# ab-berry.net
KiCad netlist of a schematic drawn in EAGLE
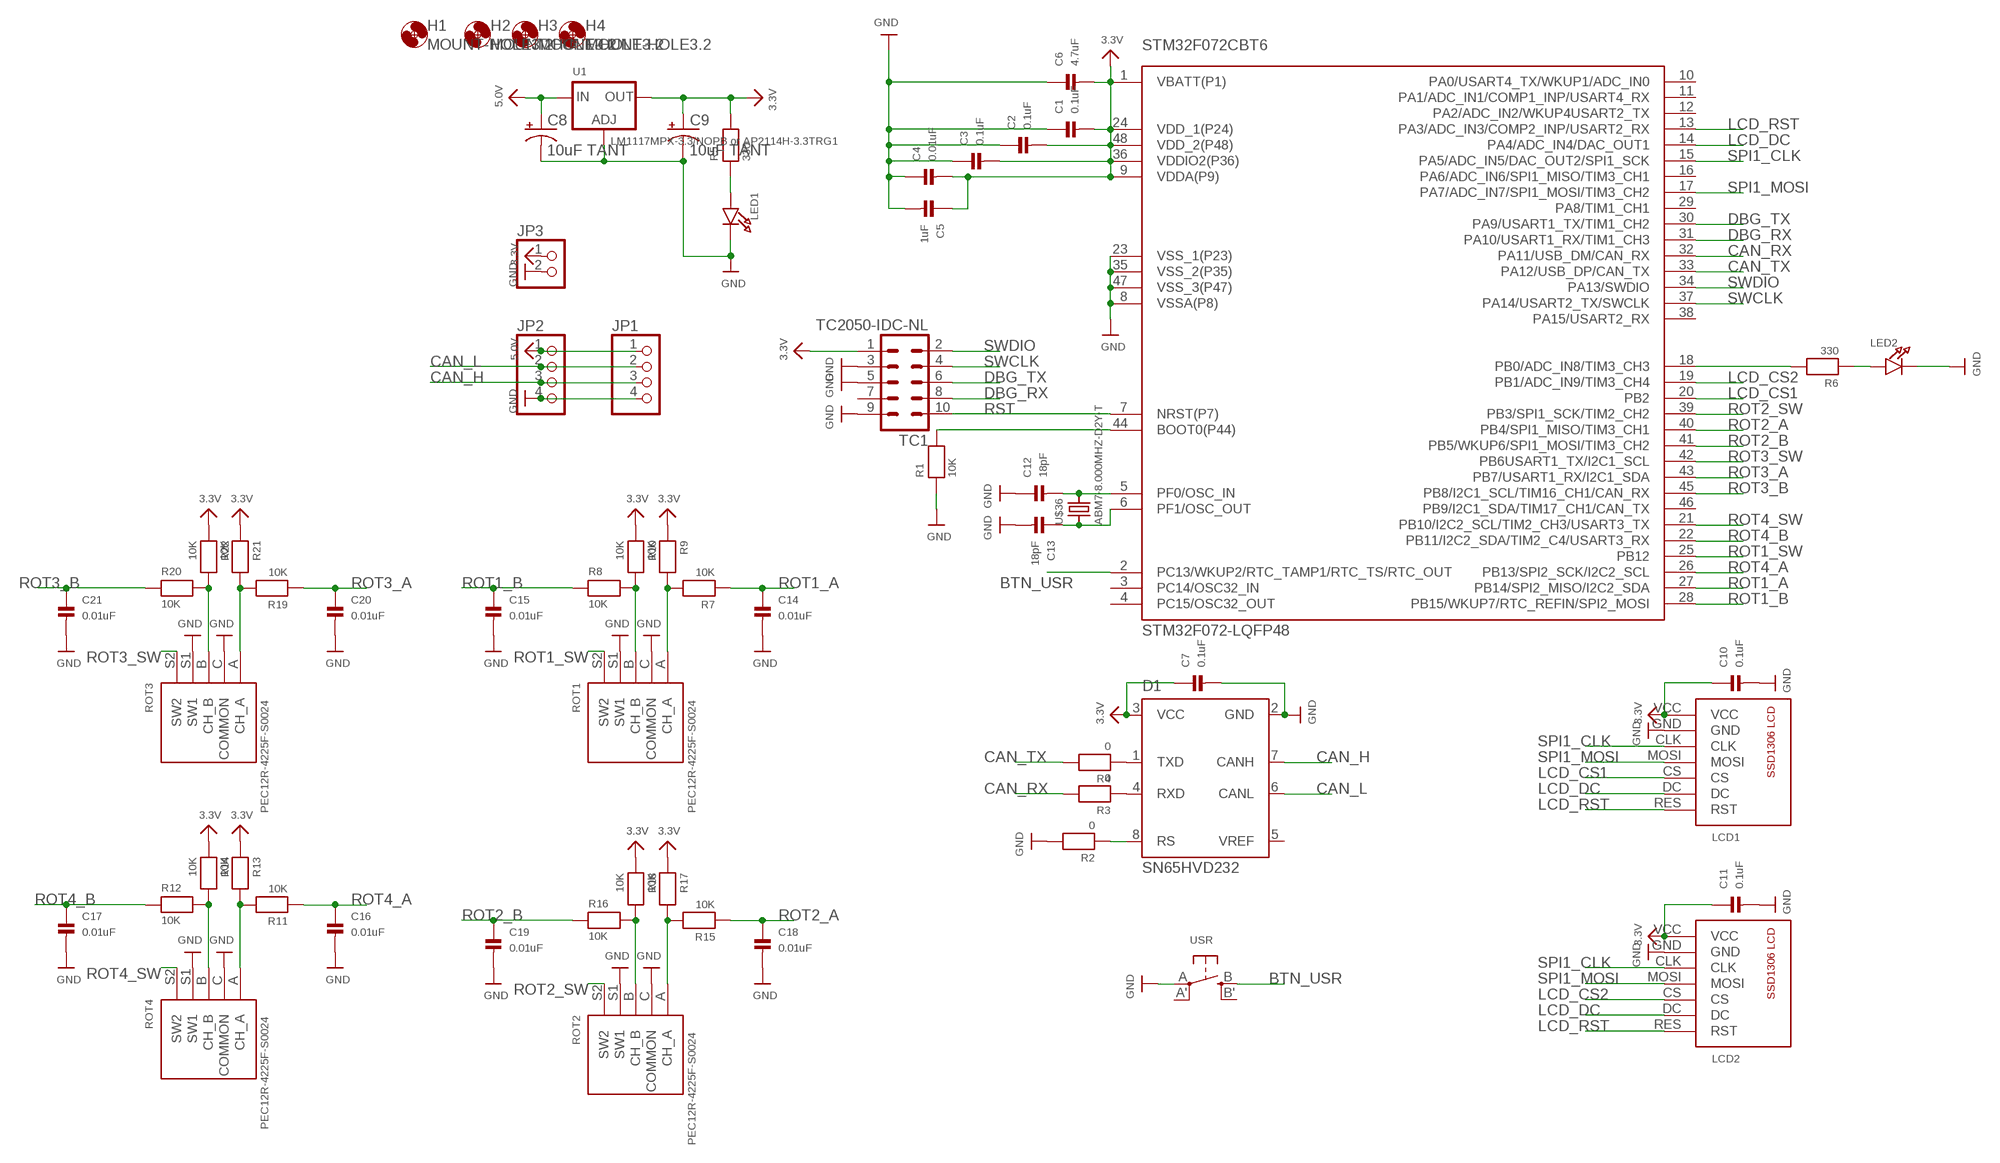
[diagram p0: schematic, sheet 1]

(export (version "E")
  (design (tool "Eeschema 10.0.6"))
  (components
    (comp (ref "C1")
      (value "0.1uF")
      (footprint "eagle-import:0603")
      (libsource (lib "eagle-import") (part "CAP_CERAMIC0603"))
    )
    (comp (ref "C2")
      (value "0.1uF")
      (footprint "eagle-import:0603")
      (libsource (lib "eagle-import") (part "CAP_CERAMIC0603"))
    )
    (comp (ref "C3")
      (value "0.1uF")
      (footprint "eagle-import:0603")
      (libsource (lib "eagle-import") (part "CAP_CERAMIC0603"))
    )
    (comp (ref "C4")
      (value "0.01uF")
      (footprint "eagle-import:0603")
      (libsource (lib "eagle-import") (part "CAP_CERAMIC0603"))
    )
    (comp (ref "C5")
      (value "1uF")
      (footprint "eagle-import:0603")
      (libsource (lib "eagle-import") (part "CAP_CERAMIC0603"))
    )
    (comp (ref "C6")
      (value "4.7uF")
      (footprint "eagle-import:0603")
      (libsource (lib "eagle-import") (part "CAP_CERAMIC0603"))
    )
    (comp (ref "C7")
      (value "0.1uF")
      (footprint "eagle-import:0603")
      (libsource (lib "eagle-import") (part "CAP_CERAMIC0603"))
    )
    (comp (ref "C8")
      (value "10uF TANT")
      (footprint "eagle-import:0603-POL")
      (libsource (lib "eagle-import") (part "10UF-6.3V-20%(0603)(TANT){dblquote}"))
    )
    (comp (ref "C9")
      (value "10uF TANT")
      (footprint "eagle-import:0603-POL")
      (libsource (lib "eagle-import") (part "10UF-6.3V-20%(0603)(TANT){dblquote}"))
    )
    (comp (ref "C10")
      (value "0.1uF")
      (footprint "eagle-import:0603")
      (libsource (lib "eagle-import") (part "CAP_CERAMIC0603"))
    )
    (comp (ref "C11")
      (value "0.1uF")
      (footprint "eagle-import:0603")
      (libsource (lib "eagle-import") (part "CAP_CERAMIC0603"))
    )
    (comp (ref "C12")
      (value "18pF")
      (footprint "eagle-import:0603")
      (libsource (lib "eagle-import") (part "CAP_CERAMIC0603"))
    )
    (comp (ref "C13")
      (value "18pF")
      (footprint "eagle-import:0603")
      (libsource (lib "eagle-import") (part "CAP_CERAMIC0603"))
    )
    (comp (ref "C14")
      (value "0.01uF")
      (footprint "eagle-import:0603")
      (libsource (lib "eagle-import") (part "CAP_CERAMIC0603"))
    )
    (comp (ref "C15")
      (value "0.01uF")
      (footprint "eagle-import:0603")
      (libsource (lib "eagle-import") (part "CAP_CERAMIC0603"))
    )
    (comp (ref "C16")
      (value "0.01uF")
      (footprint "eagle-import:0603")
      (libsource (lib "eagle-import") (part "CAP_CERAMIC0603"))
    )
    (comp (ref "C17")
      (value "0.01uF")
      (footprint "eagle-import:0603")
      (libsource (lib "eagle-import") (part "CAP_CERAMIC0603"))
    )
    (comp (ref "C18")
      (value "0.01uF")
      (footprint "eagle-import:0603")
      (libsource (lib "eagle-import") (part "CAP_CERAMIC0603"))
    )
    (comp (ref "C19")
      (value "0.01uF")
      (footprint "eagle-import:0603")
      (libsource (lib "eagle-import") (part "CAP_CERAMIC0603"))
    )
    (comp (ref "C20")
      (value "0.01uF")
      (footprint "eagle-import:0603")
      (libsource (lib "eagle-import") (part "CAP_CERAMIC0603"))
    )
    (comp (ref "C21")
      (value "0.01uF")
      (footprint "eagle-import:0603")
      (libsource (lib "eagle-import") (part "CAP_CERAMIC0603"))
    )
    (comp (ref "D1")
      (value "SN65HVD232")
      (footprint "eagle-import:SO8")
      (libsource (lib "eagle-import") (part "SN65HVD230"))
    )
    (comp (ref "H1")
      (value "MOUNT-HOLE3.2")
      (footprint "eagle-import:3,2")
      (libsource (lib "eagle-import") (part "MOUNT-HOLE3.2"))
    )
    (comp (ref "H2")
      (value "MOUNT-HOLE3.2")
      (footprint "eagle-import:3,2")
      (libsource (lib "eagle-import") (part "MOUNT-HOLE3.2"))
    )
    (comp (ref "H3")
      (value "MOUNT-HOLE3.2")
      (footprint "eagle-import:3,2")
      (libsource (lib "eagle-import") (part "MOUNT-HOLE3.2"))
    )
    (comp (ref "H4")
      (value "MOUNT-HOLE3.2")
      (footprint "eagle-import:3,2")
      (libsource (lib "eagle-import") (part "MOUNT-HOLE3.2"))
    )
    (comp (ref "JP1")
      (value "PINHD-1X4")
      (footprint "eagle-import:1X04")
      (libsource (lib "eagle-import") (part "PINHD-1X4"))
    )
    (comp (ref "JP2")
      (value "PINHD-1X4")
      (footprint "eagle-import:1X04")
      (libsource (lib "eagle-import") (part "PINHD-1X4"))
    )
    (comp (ref "JP3")
      (value "PINHD-1X2")
      (footprint "eagle-import:1X02")
      (libsource (lib "eagle-import") (part "PINHD-1X2"))
    )
    (comp (ref "LCD1")
      (value "SSD1306-7PIN")
      (footprint "eagle-import:SSD1306-7PIN")
      (libsource (lib "eagle-import") (part "SSD1306-7PIN"))
    )
    (comp (ref "LCD2")
      (value "SSD1306-7PIN")
      (footprint "eagle-import:SSD1306-7PIN")
      (libsource (lib "eagle-import") (part "SSD1306-7PIN"))
    )
    (comp (ref "LED1")
      (value "LED0603")
      (footprint "eagle-import:CHIPLED_0603")
      (libsource (lib "eagle-import") (part "LED0603"))
    )
    (comp (ref "LED2")
      (value "LED0603")
      (footprint "eagle-import:CHIPLED_0603")
      (libsource (lib "eagle-import") (part "LED0603"))
    )
    (comp (ref "R1")
      (value "10K")
      (footprint "eagle-import:0603")
      (libsource (lib "eagle-import") (part "RESISTOR0603"))
    )
    (comp (ref "R2")
      (value "0")
      (footprint "eagle-import:0603")
      (libsource (lib "eagle-import") (part "RESISTOR0603"))
    )
    (comp (ref "R3")
      (value "0")
      (footprint "eagle-import:0603")
      (libsource (lib "eagle-import") (part "RESISTOR0603"))
    )
    (comp (ref "R4")
      (value "0")
      (footprint "eagle-import:0603")
      (libsource (lib "eagle-import") (part "RESISTOR0603"))
    )
    (comp (ref "R5")
      (value "330")
      (footprint "eagle-import:0603")
      (libsource (lib "eagle-import") (part "RESISTOR0603"))
    )
    (comp (ref "R6")
      (value "330")
      (footprint "eagle-import:0603")
      (libsource (lib "eagle-import") (part "RESISTOR0603"))
    )
    (comp (ref "R7")
      (value "10K")
      (footprint "eagle-import:0603")
      (libsource (lib "eagle-import") (part "RESISTOR0603"))
    )
    (comp (ref "R8")
      (value "10K")
      (footprint "eagle-import:0603")
      (libsource (lib "eagle-import") (part "RESISTOR0603"))
    )
    (comp (ref "R9")
      (value "10K")
      (footprint "eagle-import:0603")
      (libsource (lib "eagle-import") (part "RESISTOR0603"))
    )
    (comp (ref "R10")
      (value "10K")
      (footprint "eagle-import:0603")
      (libsource (lib "eagle-import") (part "RESISTOR0603"))
    )
    (comp (ref "R11")
      (value "10K")
      (footprint "eagle-import:0603")
      (libsource (lib "eagle-import") (part "RESISTOR0603"))
    )
    (comp (ref "R12")
      (value "10K")
      (footprint "eagle-import:0603")
      (libsource (lib "eagle-import") (part "RESISTOR0603"))
    )
    (comp (ref "R13")
      (value "10K")
      (footprint "eagle-import:0603")
      (libsource (lib "eagle-import") (part "RESISTOR0603"))
    )
    (comp (ref "R14")
      (value "10K")
      (footprint "eagle-import:0603")
      (libsource (lib "eagle-import") (part "RESISTOR0603"))
    )
    (comp (ref "R15")
      (value "10K")
      (footprint "eagle-import:0603")
      (libsource (lib "eagle-import") (part "RESISTOR0603"))
    )
    (comp (ref "R16")
      (value "10K")
      (footprint "eagle-import:0603")
      (libsource (lib "eagle-import") (part "RESISTOR0603"))
    )
    (comp (ref "R17")
      (value "10K")
      (footprint "eagle-import:0603")
      (libsource (lib "eagle-import") (part "RESISTOR0603"))
    )
    (comp (ref "R18")
      (value "10K")
      (footprint "eagle-import:0603")
      (libsource (lib "eagle-import") (part "RESISTOR0603"))
    )
    (comp (ref "R19")
      (value "10K")
      (footprint "eagle-import:0603")
      (libsource (lib "eagle-import") (part "RESISTOR0603"))
    )
    (comp (ref "R20")
      (value "10K")
      (footprint "eagle-import:0603")
      (libsource (lib "eagle-import") (part "RESISTOR0603"))
    )
    (comp (ref "R21")
      (value "10K")
      (footprint "eagle-import:0603")
      (libsource (lib "eagle-import") (part "RESISTOR0603"))
    )
    (comp (ref "R22")
      (value "10K")
      (footprint "eagle-import:0603")
      (libsource (lib "eagle-import") (part "RESISTOR0603"))
    )
    (comp (ref "ROT1")
      (value "PEC12R-4225F-S0024")
      (footprint "eagle-import:PEC111-4XXXK-SXXXX")
      (libsource (lib "eagle-import") (part "PEC11-4215K-S0024"))
    )
    (comp (ref "ROT2")
      (value "PEC12R-4225F-S0024")
      (footprint "eagle-import:PEC111-4XXXK-SXXXX")
      (libsource (lib "eagle-import") (part "PEC11-4215K-S0024"))
    )
    (comp (ref "ROT3")
      (value "PEC12R-4225F-S0024")
      (footprint "eagle-import:PEC111-4XXXK-SXXXX")
      (libsource (lib "eagle-import") (part "PEC11-4215K-S0024"))
    )
    (comp (ref "ROT4")
      (value "PEC12R-4225F-S0024")
      (footprint "eagle-import:PEC111-4XXXK-SXXXX")
      (libsource (lib "eagle-import") (part "PEC11-4215K-S0024"))
    )
    (comp (ref "STM32F072CBT6")
      (value "STM32F072-LQFP48")
      (footprint "eagle-import:LQFP48")
      (libsource (lib "eagle-import") (part "STM32F072-LQFP48"))
    )
    (comp (ref "TC1")
      (value "TC2050-IDC-NL")
      (footprint "eagle-import:TC2050-IDC-NL")
      (libsource (lib "eagle-import") (part "TC2050-IDC-NL"))
    )
    (comp (ref "U$36")
      (value "ABM7-8.000MHZ-D2Y-T")
      (footprint "eagle-import:ABM7-8.000MHZ-D2Y-T")
      (libsource (lib "eagle-import") (part "ABM7-8.000MHZ-D2Y-T"))
    )
    (comp (ref "U1")
      (value "LM1117MPX-3.3/NOPB or AP2114H-3.3TRG1")
      (footprint "eagle-import:SOT223-R")
      (libsource (lib "eagle-import") (part "LM1117SOT223-REFLOW"))
    )
    (comp (ref "USR")
      (value "SWITCH_TACT_SMT")
      (footprint "eagle-import:EVQ-Q2")
      (libsource (lib "eagle-import") (part "SWITCH_TACT_SMT"))
    )
  )
  (nets
    (net (code "1") (name "/BTN_USR") (class "Default")
      (node (ref "STM32F072CBT6") (pin "2") (pinfunction "PC13/WKUP2/RTC_TAMP1/RTC_TS/RTC_OUT_2") (pintype "bidirectional"))
      (node (ref "USR") (pin "B") (pinfunction "S_B") (pintype "passive"))
    )
    (net (code "2") (name "/CAN_H") (class "Default")
      (node (ref "D1") (pin "7") (pinfunction "CANH_7") (pintype "bidirectional"))
      (node (ref "JP1") (pin "3") (pinfunction "3_3") (pintype "passive"))
      (node (ref "JP2") (pin "3") (pinfunction "3_3") (pintype "passive"))
    )
    (net (code "3") (name "/CAN_L") (class "Default")
      (node (ref "D1") (pin "6") (pinfunction "CANL_6") (pintype "bidirectional"))
      (node (ref "JP1") (pin "2") (pinfunction "2_2") (pintype "passive"))
      (node (ref "JP2") (pin "2") (pinfunction "2_2") (pintype "passive"))
    )
    (net (code "4") (name "/CAN_RX") (class "Default")
      (node (ref "R3") (pin "2") (pinfunction "2_2") (pintype "passive"))
      (node (ref "STM32F072CBT6") (pin "32") (pinfunction "PA11/USB_DM/CAN_RX_32") (pintype "bidirectional"))
    )
    (net (code "5") (name "/CAN_TX") (class "Default")
      (node (ref "R4") (pin "2") (pinfunction "2_2") (pintype "passive"))
      (node (ref "STM32F072CBT6") (pin "33") (pinfunction "PA12/USB_DP/CAN_TX_33") (pintype "bidirectional"))
    )
    (net (code "6") (name "/DBG_RX") (class "Default")
      (node (ref "STM32F072CBT6") (pin "31") (pinfunction "PA10/USART1_RX/TIM1_CH3_31") (pintype "bidirectional"))
      (node (ref "TC1") (pin "8") (pinfunction "8_8") (pintype "passive"))
    )
    (net (code "7") (name "/DBG_TX") (class "Default")
      (node (ref "STM32F072CBT6") (pin "30") (pinfunction "PA9/USART1_TX/TIM1_CH2_30") (pintype "bidirectional"))
      (node (ref "TC1") (pin "6") (pinfunction "6_6") (pintype "passive"))
    )
    (net (code "8") (name "/LCD_CS1") (class "Default")
      (node (ref "LCD1") (pin "CS") (pinfunction "CS_CS") (pintype "bidirectional"))
      (node (ref "STM32F072CBT6") (pin "20") (pinfunction "PB2_20") (pintype "bidirectional"))
    )
    (net (code "9") (name "/LCD_CS2") (class "Default")
      (node (ref "LCD2") (pin "CS") (pinfunction "CS_CS") (pintype "bidirectional"))
      (node (ref "STM32F072CBT6") (pin "19") (pinfunction "PB1/ADC_IN9/TIM3_CH4_19") (pintype "bidirectional"))
    )
    (net (code "10") (name "/LCD_DC") (class "Default")
      (node (ref "LCD1") (pin "DC") (pinfunction "DC_DC") (pintype "bidirectional"))
      (node (ref "LCD2") (pin "DC") (pinfunction "DC_DC") (pintype "bidirectional"))
      (node (ref "STM32F072CBT6") (pin "14") (pinfunction "PA4/ADC_IN4/DAC_OUT1_14") (pintype "bidirectional"))
    )
    (net (code "11") (name "/LCD_RST") (class "Default")
      (node (ref "LCD1") (pin "RES") (pinfunction "RST_RES") (pintype "bidirectional"))
      (node (ref "LCD2") (pin "RES") (pinfunction "RST_RES") (pintype "bidirectional"))
      (node (ref "STM32F072CBT6") (pin "13") (pinfunction "PA3/ADC_IN3/COMP2_INP/USART2_RX_13") (pintype "bidirectional"))
    )
    (net (code "12") (name "/ROT1_A") (class "Default")
      (node (ref "C14") (pin "1") (pinfunction "P$1_1") (pintype "passive"))
      (node (ref "R7") (pin "1") (pinfunction "1_1") (pintype "passive"))
      (node (ref "STM32F072CBT6") (pin "27") (pinfunction "PB14/SPI2_MISO/I2C2_SDA_27") (pintype "bidirectional"))
    )
    (net (code "13") (name "/ROT1_B") (class "Default")
      (node (ref "C15") (pin "1") (pinfunction "P$1_1") (pintype "passive"))
      (node (ref "R8") (pin "1") (pinfunction "1_1") (pintype "passive"))
      (node (ref "STM32F072CBT6") (pin "28") (pinfunction "PB15/WKUP7/RTC_REFIN/SPI2_MOSI_28") (pintype "bidirectional"))
    )
    (net (code "14") (name "/ROT1_SW") (class "Default")
      (node (ref "ROT1") (pin "S2") (pinfunction "SW2_S2") (pintype "bidirectional"))
      (node (ref "STM32F072CBT6") (pin "25") (pinfunction "PB12_25") (pintype "bidirectional"))
    )
    (net (code "15") (name "/ROT2_A") (class "Default")
      (node (ref "C18") (pin "1") (pinfunction "P$1_1") (pintype "passive"))
      (node (ref "R15") (pin "1") (pinfunction "1_1") (pintype "passive"))
      (node (ref "STM32F072CBT6") (pin "40") (pinfunction "PB4/SPI1_MISO/TIM3_CH1_40") (pintype "bidirectional"))
    )
    (net (code "16") (name "/ROT2_B") (class "Default")
      (node (ref "C19") (pin "1") (pinfunction "P$1_1") (pintype "passive"))
      (node (ref "R16") (pin "1") (pinfunction "1_1") (pintype "passive"))
      (node (ref "STM32F072CBT6") (pin "41") (pinfunction "PB5/WKUP6/SPI1_MOSI/TIM3_CH2_41") (pintype "bidirectional"))
    )
    (net (code "17") (name "/ROT2_SW") (class "Default")
      (node (ref "ROT2") (pin "S2") (pinfunction "SW2_S2") (pintype "bidirectional"))
      (node (ref "STM32F072CBT6") (pin "39") (pinfunction "PB3/SPI1_SCK/TIM2_CH2_39") (pintype "bidirectional"))
    )
    (net (code "18") (name "/ROT3_A") (class "Default")
      (node (ref "C20") (pin "1") (pinfunction "P$1_1") (pintype "passive"))
      (node (ref "R19") (pin "1") (pinfunction "1_1") (pintype "passive"))
      (node (ref "STM32F072CBT6") (pin "43") (pinfunction "PB7/USART1_RX/I2C1_SDA_43") (pintype "bidirectional"))
    )
    (net (code "19") (name "/ROT3_B") (class "Default")
      (node (ref "C21") (pin "1") (pinfunction "P$1_1") (pintype "passive"))
      (node (ref "R20") (pin "1") (pinfunction "1_1") (pintype "passive"))
      (node (ref "STM32F072CBT6") (pin "45") (pinfunction "PB8/I2C1_SCL/TIM16_CH1/CAN_RX_45") (pintype "bidirectional"))
    )
    (net (code "20") (name "/ROT3_SW") (class "Default")
      (node (ref "ROT3") (pin "S2") (pinfunction "SW2_S2") (pintype "bidirectional"))
      (node (ref "STM32F072CBT6") (pin "42") (pinfunction "PB6USART1_TX/I2C1_SCL_42") (pintype "bidirectional"))
    )
    (net (code "21") (name "/ROT4_A") (class "Default")
      (node (ref "C16") (pin "1") (pinfunction "P$1_1") (pintype "passive"))
      (node (ref "R11") (pin "1") (pinfunction "1_1") (pintype "passive"))
      (node (ref "STM32F072CBT6") (pin "26") (pinfunction "PB13/SPI2_SCK/I2C2_SCL_26") (pintype "bidirectional"))
    )
    (net (code "22") (name "/ROT4_B") (class "Default")
      (node (ref "C17") (pin "1") (pinfunction "P$1_1") (pintype "passive"))
      (node (ref "R12") (pin "1") (pinfunction "1_1") (pintype "passive"))
      (node (ref "STM32F072CBT6") (pin "22") (pinfunction "PB11/I2C2_SDA/TIM2_C4/USART3_RX_22") (pintype "bidirectional"))
    )
    (net (code "23") (name "/ROT4_SW") (class "Default")
      (node (ref "ROT4") (pin "S2") (pinfunction "SW2_S2") (pintype "bidirectional"))
      (node (ref "STM32F072CBT6") (pin "21") (pinfunction "PB10/I2C2_SCL/TIM2_CH3/USART3_TX_21") (pintype "bidirectional"))
    )
    (net (code "24") (name "/RST") (class "Default")
      (node (ref "STM32F072CBT6") (pin "7") (pinfunction "NRST(P7)_7") (pintype "bidirectional"))
      (node (ref "TC1") (pin "10") (pinfunction "10_10") (pintype "passive"))
    )
    (net (code "25") (name "/SPI1_CLK") (class "Default")
      (node (ref "LCD1") (pin "CLK") (pinfunction "CLK_CLK") (pintype "bidirectional"))
      (node (ref "LCD2") (pin "CLK") (pinfunction "CLK_CLK") (pintype "bidirectional"))
      (node (ref "STM32F072CBT6") (pin "15") (pinfunction "PA5/ADC_IN5/DAC_OUT2/SPI1_SCK_15") (pintype "bidirectional"))
    )
    (net (code "26") (name "/SPI1_MOSI") (class "Default")
      (node (ref "LCD1") (pin "MOSI") (pinfunction "MOSI_MOSI") (pintype "bidirectional"))
      (node (ref "LCD2") (pin "MOSI") (pinfunction "MOSI_MOSI") (pintype "bidirectional"))
      (node (ref "STM32F072CBT6") (pin "17") (pinfunction "PA7/ADC_IN7/SPI1_MOSI/TIM3_CH2_17") (pintype "bidirectional"))
    )
    (net (code "27") (name "/SWCLK") (class "Default")
      (node (ref "STM32F072CBT6") (pin "37") (pinfunction "PA14/USART2_TX/SWCLK_37") (pintype "bidirectional"))
      (node (ref "TC1") (pin "4") (pinfunction "4_4") (pintype "passive"))
    )
    (net (code "28") (name "/SWDIO") (class "Default")
      (node (ref "STM32F072CBT6") (pin "34") (pinfunction "PA13/SWDIO_34") (pintype "bidirectional"))
      (node (ref "TC1") (pin "2") (pinfunction "2_2") (pintype "passive"))
    )
    (net (code "29") (name "3.3V") (class "Default")
      (node (ref "C1") (pin "2") (pinfunction "P$2_2") (pintype "passive"))
      (node (ref "C10") (pin "1") (pinfunction "P$1_1") (pintype "passive"))
      (node (ref "C11") (pin "1") (pinfunction "P$1_1") (pintype "passive"))
      (node (ref "C2") (pin "2") (pinfunction "P$2_2") (pintype "passive"))
      (node (ref "C3") (pin "2") (pinfunction "P$2_2") (pintype "passive"))
      (node (ref "C4") (pin "2") (pinfunction "P$2_2") (pintype "passive"))
      (node (ref "C5") (pin "1") (pinfunction "P$1_1") (pintype "passive"))
      (node (ref "C6") (pin "2") (pinfunction "P$2_2") (pintype "passive"))
      (node (ref "C7") (pin "1") (pinfunction "P$1_1") (pintype "passive"))
      (node (ref "C9") (pin "A") (pinfunction "+_A") (pintype "passive"))
      (node (ref "D1") (pin "3") (pinfunction "VCC_3") (pintype "power_in"))
      (node (ref "JP3") (pin "1") (pinfunction "1_1") (pintype "passive"))
      (node (ref "LCD1") (pin "VCC") (pinfunction "VCC_VCC") (pintype "bidirectional"))
      (node (ref "LCD2") (pin "VCC") (pinfunction "VCC_VCC") (pintype "bidirectional"))
      (node (ref "R10") (pin "1") (pinfunction "1_1") (pintype "passive"))
      (node (ref "R13") (pin "1") (pinfunction "1_1") (pintype "passive"))
      (node (ref "R14") (pin "1") (pinfunction "1_1") (pintype "passive"))
      (node (ref "R17") (pin "1") (pinfunction "1_1") (pintype "passive"))
      (node (ref "R18") (pin "1") (pinfunction "1_1") (pintype "passive"))
      (node (ref "R21") (pin "1") (pinfunction "1_1") (pintype "passive"))
      (node (ref "R22") (pin "1") (pinfunction "1_1") (pintype "passive"))
      (node (ref "R5") (pin "2") (pinfunction "2_2") (pintype "passive"))
      (node (ref "R9") (pin "1") (pinfunction "1_1") (pintype "passive"))
      (node (ref "STM32F072CBT6") (pin "1") (pinfunction "VBATT(P1)_1") (pintype "bidirectional"))
      (node (ref "STM32F072CBT6") (pin "24") (pinfunction "VDD_1(P24)_24") (pintype "bidirectional"))
      (node (ref "STM32F072CBT6") (pin "36") (pinfunction "VDDIO2(P36)_36") (pintype "bidirectional"))
      (node (ref "STM32F072CBT6") (pin "48") (pinfunction "VDD_2(P48)_48") (pintype "bidirectional"))
      (node (ref "STM32F072CBT6") (pin "9") (pinfunction "VDDA(P9)_9") (pintype "bidirectional"))
      (node (ref "TC1") (pin "1") (pinfunction "1_1") (pintype "passive"))
      (node (ref "U1") (pin "2") (pinfunction "OUT_2") (pintype "passive"))
    )
    (net (code "30") (name "5.0V") (class "Default")
      (node (ref "C8") (pin "A") (pinfunction "+_A") (pintype "passive"))
      (node (ref "JP1") (pin "1") (pinfunction "1_1") (pintype "passive"))
      (node (ref "JP2") (pin "1") (pinfunction "1_1") (pintype "passive"))
      (node (ref "U1") (pin "3") (pinfunction "IN_3") (pintype "input"))
    )
    (net (code "31") (name "GND") (class "Default")
      (node (ref "C1") (pin "1") (pinfunction "P$1_1") (pintype "passive"))
      (node (ref "C10") (pin "2") (pinfunction "P$2_2") (pintype "passive"))
      (node (ref "C11") (pin "2") (pinfunction "P$2_2") (pintype "passive"))
      (node (ref "C12") (pin "1") (pinfunction "P$1_1") (pintype "passive"))
      (node (ref "C13") (pin "2") (pinfunction "P$2_2") (pintype "passive"))
      (node (ref "C14") (pin "2") (pinfunction "P$2_2") (pintype "passive"))
      (node (ref "C15") (pin "2") (pinfunction "P$2_2") (pintype "passive"))
      (node (ref "C16") (pin "2") (pinfunction "P$2_2") (pintype "passive"))
      (node (ref "C17") (pin "2") (pinfunction "P$2_2") (pintype "passive"))
      (node (ref "C18") (pin "2") (pinfunction "P$2_2") (pintype "passive"))
      (node (ref "C19") (pin "2") (pinfunction "P$2_2") (pintype "passive"))
      (node (ref "C2") (pin "1") (pinfunction "P$1_1") (pintype "passive"))
      (node (ref "C20") (pin "2") (pinfunction "P$2_2") (pintype "passive"))
      (node (ref "C21") (pin "2") (pinfunction "P$2_2") (pintype "passive"))
      (node (ref "C3") (pin "1") (pinfunction "P$1_1") (pintype "passive"))
      (node (ref "C4") (pin "1") (pinfunction "P$1_1") (pintype "passive"))
      (node (ref "C5") (pin "2") (pinfunction "P$2_2") (pintype "passive"))
      (node (ref "C6") (pin "1") (pinfunction "P$1_1") (pintype "passive"))
      (node (ref "C7") (pin "2") (pinfunction "P$2_2") (pintype "passive"))
      (node (ref "C8") (pin "K") (pinfunction "-_K") (pintype "passive"))
      (node (ref "C9") (pin "K") (pinfunction "-_K") (pintype "passive"))
      (node (ref "D1") (pin "2") (pinfunction "GND_2") (pintype "power_in"))
      (node (ref "JP1") (pin "4") (pinfunction "4_4") (pintype "passive"))
      (node (ref "JP2") (pin "4") (pinfunction "4_4") (pintype "passive"))
      (node (ref "JP3") (pin "2") (pinfunction "2_2") (pintype "passive"))
      (node (ref "LCD1") (pin "GND") (pinfunction "GND_GND") (pintype "bidirectional"))
      (node (ref "LCD2") (pin "GND") (pinfunction "GND_GND") (pintype "bidirectional"))
      (node (ref "LED1") (pin "C") (pinfunction "C_C") (pintype "passive"))
      (node (ref "LED2") (pin "C") (pinfunction "C_C") (pintype "passive"))
      (node (ref "R1") (pin "1") (pinfunction "1_1") (pintype "passive"))
      (node (ref "R2") (pin "2") (pinfunction "2_2") (pintype "passive"))
      (node (ref "ROT1") (pin "C") (pinfunction "COMMON_C") (pintype "input"))
      (node (ref "ROT1") (pin "S1") (pinfunction "SW1_S1") (pintype "bidirectional"))
      (node (ref "ROT2") (pin "C") (pinfunction "COMMON_C") (pintype "input"))
      (node (ref "ROT2") (pin "S1") (pinfunction "SW1_S1") (pintype "bidirectional"))
      (node (ref "ROT3") (pin "C") (pinfunction "COMMON_C") (pintype "input"))
      (node (ref "ROT3") (pin "S1") (pinfunction "SW1_S1") (pintype "bidirectional"))
      (node (ref "ROT4") (pin "C") (pinfunction "COMMON_C") (pintype "input"))
      (node (ref "ROT4") (pin "S1") (pinfunction "SW1_S1") (pintype "bidirectional"))
      (node (ref "STM32F072CBT6") (pin "23") (pinfunction "VSS_1(P23)_23") (pintype "bidirectional"))
      (node (ref "STM32F072CBT6") (pin "35") (pinfunction "VSS_2(P35)_35") (pintype "bidirectional"))
      (node (ref "STM32F072CBT6") (pin "47") (pinfunction "VSS_3(P47)_47") (pintype "bidirectional"))
      (node (ref "STM32F072CBT6") (pin "8") (pinfunction "VSSA(P8)_8") (pintype "bidirectional"))
      (node (ref "TC1") (pin "3") (pinfunction "3_3") (pintype "passive"))
      (node (ref "TC1") (pin "5") (pinfunction "5_5") (pintype "passive"))
      (node (ref "TC1") (pin "9") (pinfunction "9_9") (pintype "passive"))
      (node (ref "U1") (pin "1") (pinfunction "ADJ_1") (pintype "input"))
      (node (ref "USR") (pin "A") (pinfunction "P_A") (pintype "passive"))
    )
    (net (code "32") (name "Net-(C12-P$2)") (class "Default")
      (node (ref "C12") (pin "2") (pinfunction "P$2_2") (pintype "passive"))
      (node (ref "STM32F072CBT6") (pin "5") (pinfunction "PF0/OSC_IN_5") (pintype "bidirectional"))
      (node (ref "U$36") (pin "P$2") (pinfunction "2_P$2") (pintype "passive"))
    )
    (net (code "33") (name "Net-(C13-P$1)") (class "Default")
      (node (ref "C13") (pin "1") (pinfunction "P$1_1") (pintype "passive"))
      (node (ref "STM32F072CBT6") (pin "6") (pinfunction "PF1/OSC_OUT_6") (pintype "bidirectional"))
      (node (ref "U$36") (pin "P$1") (pinfunction "1_P$1") (pintype "passive"))
    )
    (net (code "34") (name "Net-(D1-RS)") (class "Default")
      (node (ref "D1") (pin "8") (pinfunction "RS_8") (pintype "input"))
      (node (ref "R2") (pin "1") (pinfunction "1_1") (pintype "passive"))
    )
    (net (code "35") (name "Net-(D1-RXD)") (class "Default")
      (node (ref "D1") (pin "4") (pinfunction "RXD_4") (pintype "output"))
      (node (ref "R3") (pin "1") (pinfunction "1_1") (pintype "passive"))
    )
    (net (code "36") (name "Net-(D1-TXD)") (class "Default")
      (node (ref "D1") (pin "1") (pinfunction "TXD_1") (pintype "input"))
      (node (ref "R4") (pin "1") (pinfunction "1_1") (pintype "passive"))
    )
    (net (code "37") (name "Net-(LED1-PadA)") (class "Default")
      (node (ref "LED1") (pin "A") (pinfunction "A_A") (pintype "passive"))
      (node (ref "R5") (pin "1") (pinfunction "1_1") (pintype "passive"))
    )
    (net (code "38") (name "Net-(LED2-PadA)") (class "Default")
      (node (ref "LED2") (pin "A") (pinfunction "A_A") (pintype "passive"))
      (node (ref "R6") (pin "1") (pinfunction "1_1") (pintype "passive"))
    )
    (net (code "39") (name "Net-(ROT1-CH_A)") (class "Default")
      (node (ref "R7") (pin "2") (pinfunction "2_2") (pintype "passive"))
      (node (ref "R9") (pin "2") (pinfunction "2_2") (pintype "passive"))
      (node (ref "ROT1") (pin "A") (pinfunction "CH_A_A") (pintype "output"))
    )
    (net (code "40") (name "Net-(ROT1-CH_B)") (class "Default")
      (node (ref "R10") (pin "2") (pinfunction "2_2") (pintype "passive"))
      (node (ref "R8") (pin "2") (pinfunction "2_2") (pintype "passive"))
      (node (ref "ROT1") (pin "B") (pinfunction "CH_B_B") (pintype "output"))
    )
    (net (code "41") (name "Net-(ROT2-CH_A)") (class "Default")
      (node (ref "R15") (pin "2") (pinfunction "2_2") (pintype "passive"))
      (node (ref "R17") (pin "2") (pinfunction "2_2") (pintype "passive"))
      (node (ref "ROT2") (pin "A") (pinfunction "CH_A_A") (pintype "output"))
    )
    (net (code "42") (name "Net-(ROT2-CH_B)") (class "Default")
      (node (ref "R16") (pin "2") (pinfunction "2_2") (pintype "passive"))
      (node (ref "R18") (pin "2") (pinfunction "2_2") (pintype "passive"))
      (node (ref "ROT2") (pin "B") (pinfunction "CH_B_B") (pintype "output"))
    )
    (net (code "43") (name "Net-(ROT3-CH_A)") (class "Default")
      (node (ref "R19") (pin "2") (pinfunction "2_2") (pintype "passive"))
      (node (ref "R21") (pin "2") (pinfunction "2_2") (pintype "passive"))
      (node (ref "ROT3") (pin "A") (pinfunction "CH_A_A") (pintype "output"))
    )
    (net (code "44") (name "Net-(ROT3-CH_B)") (class "Default")
      (node (ref "R20") (pin "2") (pinfunction "2_2") (pintype "passive"))
      (node (ref "R22") (pin "2") (pinfunction "2_2") (pintype "passive"))
      (node (ref "ROT3") (pin "B") (pinfunction "CH_B_B") (pintype "output"))
    )
    (net (code "45") (name "Net-(ROT4-CH_A)") (class "Default")
      (node (ref "R11") (pin "2") (pinfunction "2_2") (pintype "passive"))
      (node (ref "R13") (pin "2") (pinfunction "2_2") (pintype "passive"))
      (node (ref "ROT4") (pin "A") (pinfunction "CH_A_A") (pintype "output"))
    )
    (net (code "46") (name "Net-(ROT4-CH_B)") (class "Default")
      (node (ref "R12") (pin "2") (pinfunction "2_2") (pintype "passive"))
      (node (ref "R14") (pin "2") (pinfunction "2_2") (pintype "passive"))
      (node (ref "ROT4") (pin "B") (pinfunction "CH_B_B") (pintype "output"))
    )
    (net (code "47") (name "Net-(STM32F072CBT6-BOOT0(P44))") (class "Default")
      (node (ref "R1") (pin "2") (pinfunction "2_2") (pintype "passive"))
      (node (ref "STM32F072CBT6") (pin "44") (pinfunction "BOOT0(P44)_44") (pintype "bidirectional"))
    )
    (net (code "48") (name "Net-(STM32F072CBT6-PB0{slash}ADC_IN8{slash}TIM3_CH3)") (class "Default")
      (node (ref "R6") (pin "2") (pinfunction "2_2") (pintype "passive"))
      (node (ref "STM32F072CBT6") (pin "18") (pinfunction "PB0/ADC_IN8/TIM3_CH3_18") (pintype "bidirectional"))
    )
    (net (code "49") (name "unconnected-(D1-VREF-Pad5)") (class "Default")
      (node (ref "D1") (pin "5") (pinfunction "VREF_5") (pintype "output"))
    )
    (net (code "50") (name "unconnected-(STM32F072CBT6-PA0{slash}USART4_TX{slash}WKUP1{slash}ADC_IN0-Pad10)") (class "Default")
      (node (ref "STM32F072CBT6") (pin "10") (pinfunction "PA0/USART4_TX/WKUP1/ADC_IN0_10") (pintype "bidirectional"))
    )
    (net (code "51") (name "unconnected-(STM32F072CBT6-PA1{slash}ADC_IN1{slash}COMP1_INP{slash}USART4_RX-Pad11)") (class "Default")
      (node (ref "STM32F072CBT6") (pin "11") (pinfunction "PA1/ADC_IN1/COMP1_INP/USART4_RX_11") (pintype "bidirectional"))
    )
    (net (code "52") (name "unconnected-(STM32F072CBT6-PA2{slash}ADC_IN2{slash}WKUP4USART2_TX-Pad12)") (class "Default")
      (node (ref "STM32F072CBT6") (pin "12") (pinfunction "PA2/ADC_IN2/WKUP4USART2_TX_12") (pintype "bidirectional"))
    )
    (net (code "53") (name "unconnected-(STM32F072CBT6-PA6{slash}ADC_IN6{slash}SPI1_MISO{slash}TIM3_CH1-Pad16)") (class "Default")
      (node (ref "STM32F072CBT6") (pin "16") (pinfunction "PA6/ADC_IN6/SPI1_MISO/TIM3_CH1_16") (pintype "bidirectional"))
    )
    (net (code "54") (name "unconnected-(STM32F072CBT6-PA8{slash}TIM1_CH1-Pad29)") (class "Default")
      (node (ref "STM32F072CBT6") (pin "29") (pinfunction "PA8/TIM1_CH1_29") (pintype "bidirectional"))
    )
    (net (code "55") (name "unconnected-(STM32F072CBT6-PA15{slash}USART2_RX-Pad38)") (class "Default")
      (node (ref "STM32F072CBT6") (pin "38") (pinfunction "PA15/USART2_RX_38") (pintype "bidirectional"))
    )
    (net (code "56") (name "unconnected-(STM32F072CBT6-PB9{slash}I2C1_SDA{slash}TIM17_CH1{slash}CAN_TX-Pad46)") (class "Default")
      (node (ref "STM32F072CBT6") (pin "46") (pinfunction "PB9/I2C1_SDA/TIM17_CH1/CAN_TX_46") (pintype "bidirectional"))
    )
    (net (code "57") (name "unconnected-(STM32F072CBT6-PC14{slash}OSC32_IN-Pad3)") (class "Default")
      (node (ref "STM32F072CBT6") (pin "3") (pinfunction "PC14/OSC32_IN_3") (pintype "bidirectional"))
    )
    (net (code "58") (name "unconnected-(STM32F072CBT6-PC15{slash}OSC32_OUT-Pad4)") (class "Default")
      (node (ref "STM32F072CBT6") (pin "4") (pinfunction "PC15/OSC32_OUT_4") (pintype "bidirectional"))
    )
    (net (code "59") (name "unconnected-(TC1-Pad7)") (class "Default")
      (node (ref "TC1") (pin "7") (pinfunction "7_7") (pintype "passive"))
    )
    (net (code "60") (name "unconnected-(USR-P1-PadA')") (class "Default")
      (node (ref "USR") (pin "A'") (pinfunction "P1_A'") (pintype "passive"))
    )
    (net (code "61") (name "unconnected-(USR-S1-PadB')") (class "Default")
      (node (ref "USR") (pin "B'") (pinfunction "S1_B'") (pintype "passive"))
    )
  )
)
